# SNAC_7ch_SNES_in_Housing.net
KiCad netlist of a schematic drawn in EAGLE
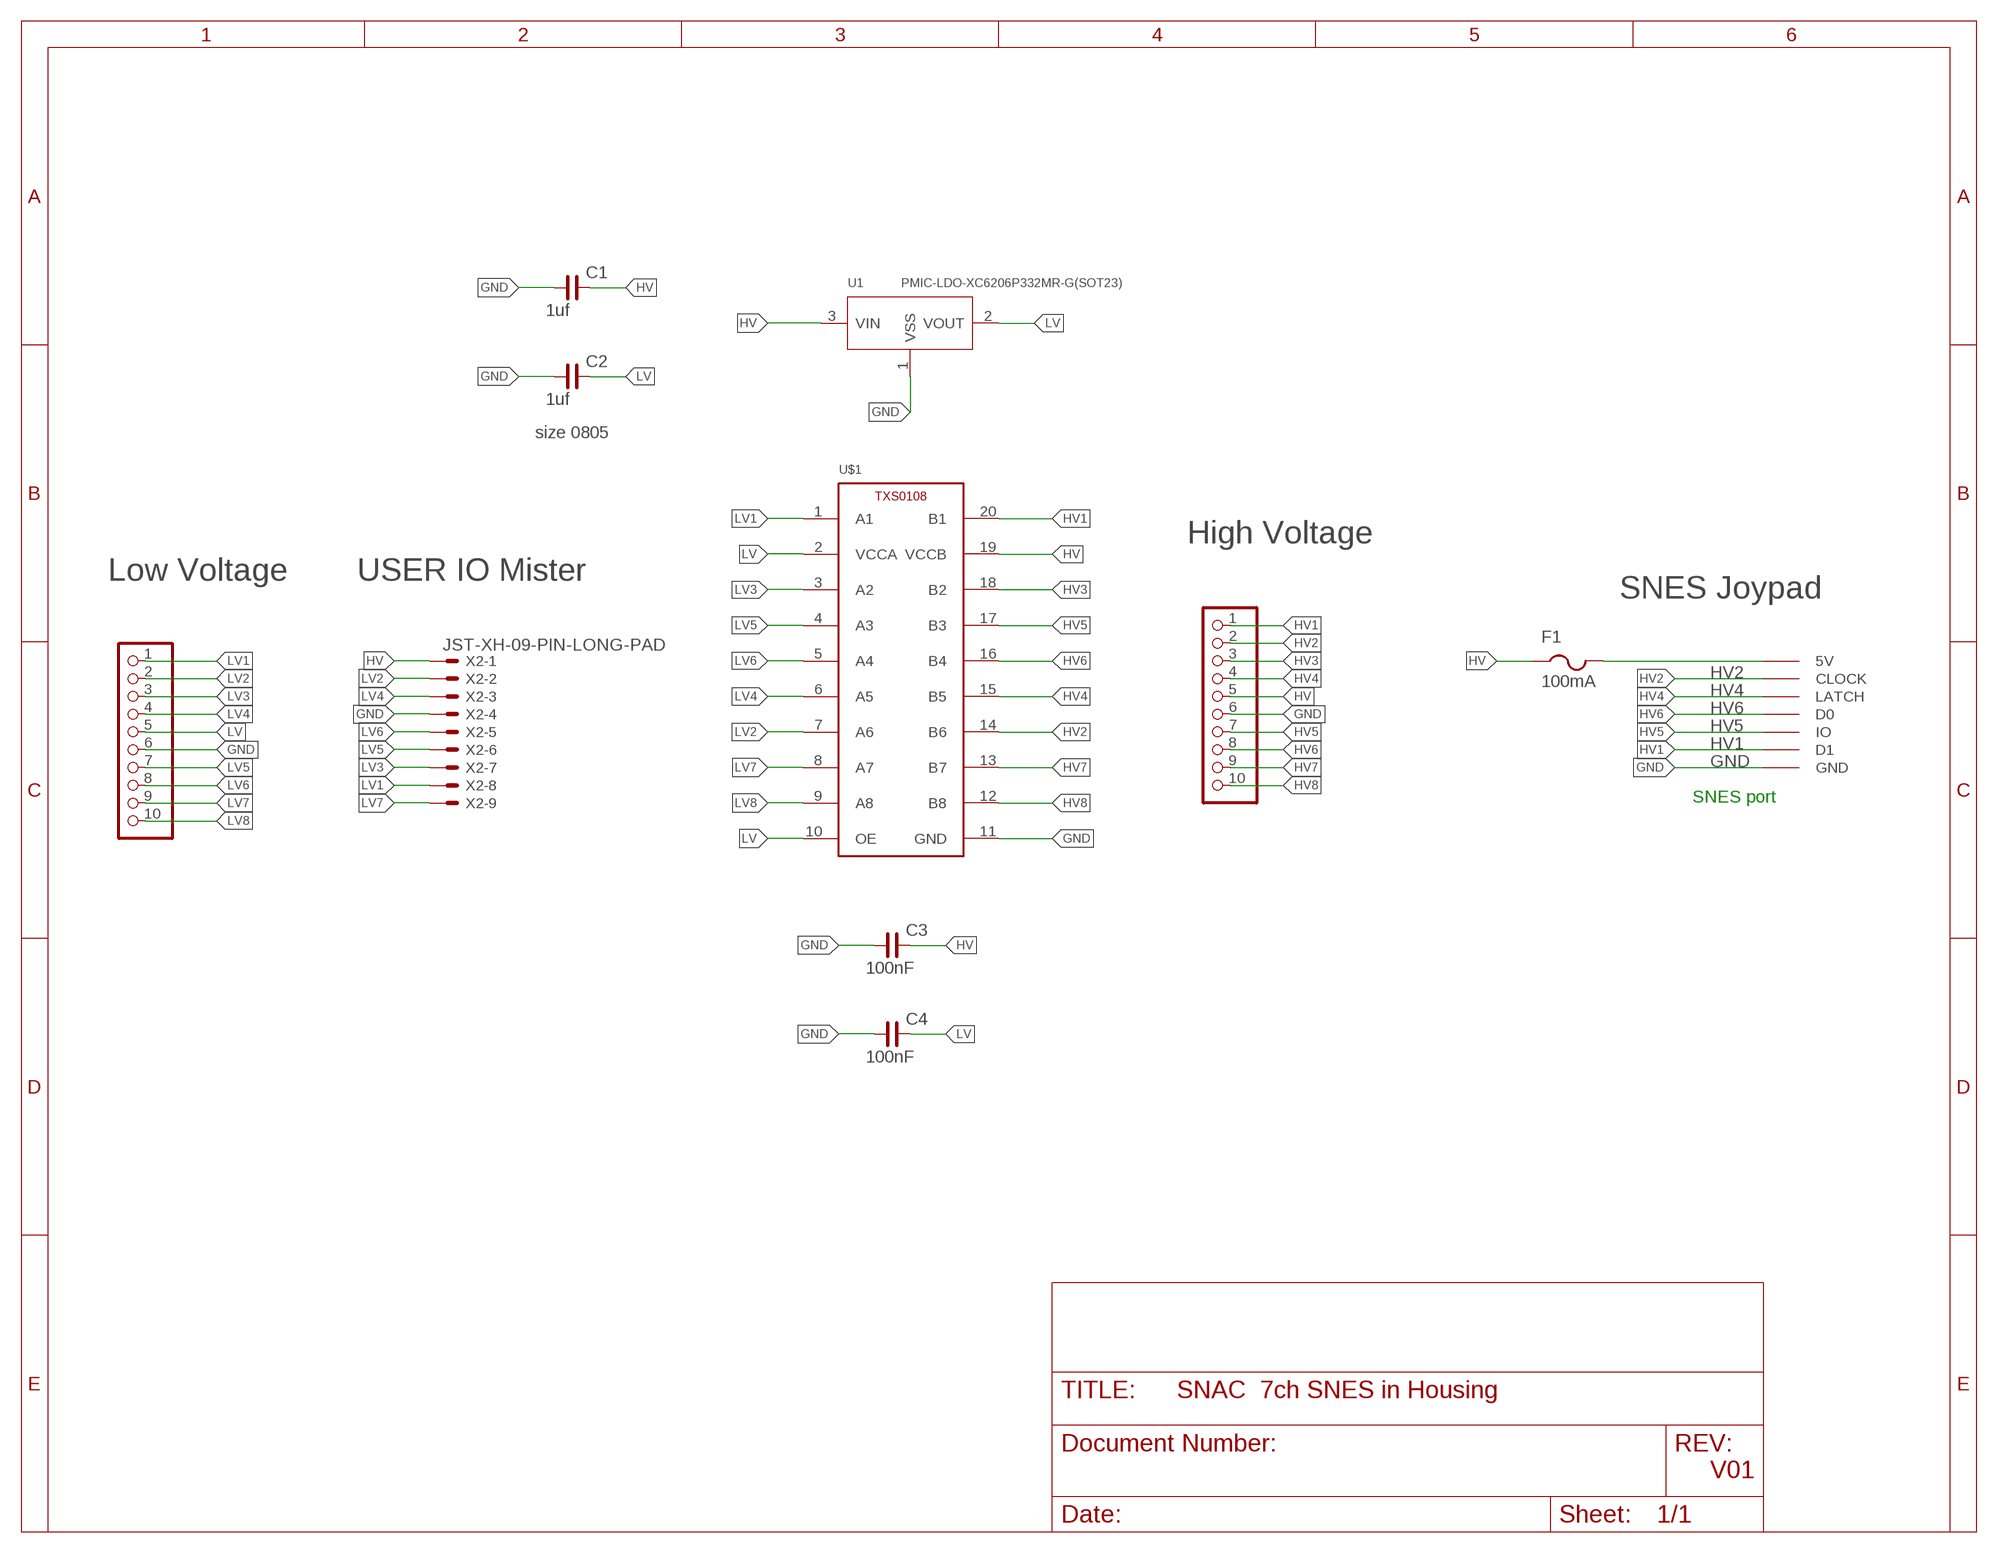
[diagram p0: schematic, sheet 1]

(export (version "E")
  (design (tool "Eeschema 10.0.6"))
  (components
    (comp (ref "C1")
      (value "1uf")
      (footprint "eagle-import:C0805")
      (libsource (lib "eagle-import") (part "C_0805"))
    )
    (comp (ref "C2")
      (value "1uf")
      (footprint "eagle-import:C0805")
      (libsource (lib "eagle-import") (part "C_0805"))
    )
    (comp (ref "C3")
      (value "100nF")
      (footprint "eagle-import:C0805")
      (libsource (lib "eagle-import") (part "C_0805"))
    )
    (comp (ref "C4")
      (value "100nF")
      (footprint "eagle-import:C0805")
      (libsource (lib "eagle-import") (part "C_0805"))
    )
    (comp (ref "F1")
      (value "100mA")
      (footprint "eagle-import:R1206")
      (libsource (lib "eagle-import") (part "PTCFUSE-1206"))
    )
    (comp (ref "JP1")
      (value "PINHD-1X10_2.54-S")
      (footprint "eagle-import:1X10-S")
      (libsource (lib "eagle-import") (part "PINHD-1X10_2.54-S"))
    )
    (comp (ref "JP2")
      (value "PINHD-1X10_2.54-S")
      (footprint "eagle-import:1X10-S")
      (libsource (lib "eagle-import") (part "PINHD-1X10_2.54-S"))
    )
    (comp (ref "U$1")
      (value "TXS0108")
      (footprint "eagle-import:R-PUSON-N20")
      (libsource (lib "eagle-import") (part "TXS0108"))
    )
    (comp (ref "U$3")
      (value "SNESCONN")
      (footprint "eagle-import:SNESCONN")
      (libsource (lib "eagle-import") (part "SNESCONN"))
    )
    (comp (ref "U1")
      (value "PMIC-LDO-XC6206P332MR-G(SOT23)")
      (footprint "eagle-import:SOT-23")
      (fields (field (name "MF") "Torex") (field (name "MP") "XC6206P332MR-G"))
      (libsource (lib "eagle-import") (part "PMIC-LDO-XC6206P332MR-G(SOT23)"))
    )
    (comp (ref "X2")
      (value "JST-XH-09-PIN-LONG-PAD")
      (footprint "eagle-import:JST-XH-09-PACKAGE-LONG-PAD")
      (libsource (lib "eagle-import") (part "JST-XH-09-PIN-LONG-PAD"))
    )
  )
  (nets
    (net (code "1") (name "GND") (class "Default")
      (node (ref "C1") (pin "1") (pinfunction "1_1") (pintype "passive"))
      (node (ref "C2") (pin "1") (pinfunction "1_1") (pintype "passive"))
      (node (ref "C3") (pin "1") (pinfunction "1_1") (pintype "passive"))
      (node (ref "C4") (pin "1") (pinfunction "1_1") (pintype "passive"))
      (node (ref "JP1") (pin "6") (pinfunction "6_6") (pintype "passive"))
      (node (ref "JP2") (pin "6") (pinfunction "6_6") (pintype "passive"))
      (node (ref "U$1") (pin "11") (pinfunction "GND_11") (pintype "bidirectional"))
      (node (ref "U$3") (pin "GND") (pinfunction "GND_GND") (pintype "power_in"))
      (node (ref "U1") (pin "1") (pinfunction "VSS_1") (pintype "power_in"))
      (node (ref "X2") (pin "4") (pinfunction "S_4") (pintype "passive"))
    )
    (net (code "2") (name "HV") (class "Default")
      (node (ref "C1") (pin "2") (pinfunction "2_2") (pintype "passive"))
      (node (ref "C3") (pin "2") (pinfunction "2_2") (pintype "passive"))
      (node (ref "F1") (pin "1") (pinfunction "1_1") (pintype "passive"))
      (node (ref "JP2") (pin "5") (pinfunction "5_5") (pintype "passive"))
      (node (ref "U$1") (pin "19") (pinfunction "VCCB_19") (pintype "bidirectional"))
      (node (ref "U1") (pin "3") (pinfunction "VIN_3") (pintype "input"))
      (node (ref "X2") (pin "1") (pinfunction "S_1") (pintype "passive"))
    )
    (net (code "3") (name "HV1") (class "Default")
      (node (ref "JP2") (pin "1") (pinfunction "1_1") (pintype "passive"))
      (node (ref "U$1") (pin "20") (pinfunction "B1_20") (pintype "bidirectional"))
      (node (ref "U$3") (pin "D1") (pinfunction "D1_D1") (pintype "bidirectional"))
    )
    (net (code "4") (name "HV2") (class "Default")
      (node (ref "JP2") (pin "2") (pinfunction "2_2") (pintype "passive"))
      (node (ref "U$1") (pin "14") (pinfunction "B6_14") (pintype "bidirectional"))
      (node (ref "U$3") (pin "CLOCK") (pinfunction "CLOCK_CLOCK") (pintype "input"))
    )
    (net (code "5") (name "HV3") (class "Default")
      (node (ref "JP2") (pin "3") (pinfunction "3_3") (pintype "passive"))
      (node (ref "U$1") (pin "18") (pinfunction "B2_18") (pintype "bidirectional"))
    )
    (net (code "6") (name "HV4") (class "Default")
      (node (ref "JP2") (pin "4") (pinfunction "4_4") (pintype "passive"))
      (node (ref "U$1") (pin "15") (pinfunction "B5_15") (pintype "bidirectional"))
      (node (ref "U$3") (pin "LATCH") (pinfunction "LATCH_LATCH") (pintype "input"))
    )
    (net (code "7") (name "HV5") (class "Default")
      (node (ref "JP2") (pin "7") (pinfunction "7_7") (pintype "passive"))
      (node (ref "U$1") (pin "17") (pinfunction "B3_17") (pintype "bidirectional"))
      (node (ref "U$3") (pin "IO") (pinfunction "IO_IO") (pintype "bidirectional"))
    )
    (net (code "8") (name "HV6") (class "Default")
      (node (ref "JP2") (pin "8") (pinfunction "8_8") (pintype "passive"))
      (node (ref "U$1") (pin "16") (pinfunction "B4_16") (pintype "bidirectional"))
      (node (ref "U$3") (pin "D0") (pinfunction "D0_D0") (pintype "bidirectional"))
    )
    (net (code "9") (name "HV7") (class "Default")
      (node (ref "JP2") (pin "9") (pinfunction "9_9") (pintype "passive"))
      (node (ref "U$1") (pin "13") (pinfunction "B7_13") (pintype "bidirectional"))
    )
    (net (code "10") (name "HV8") (class "Default")
      (node (ref "JP2") (pin "10") (pinfunction "10_10") (pintype "passive"))
      (node (ref "U$1") (pin "12") (pinfunction "B8_12") (pintype "bidirectional"))
    )
    (net (code "11") (name "LV") (class "Default")
      (node (ref "C2") (pin "2") (pinfunction "2_2") (pintype "passive"))
      (node (ref "C4") (pin "2") (pinfunction "2_2") (pintype "passive"))
      (node (ref "JP1") (pin "5") (pinfunction "5_5") (pintype "passive"))
      (node (ref "U$1") (pin "10") (pinfunction "OE_10") (pintype "bidirectional"))
      (node (ref "U$1") (pin "2") (pinfunction "VCCA_2") (pintype "bidirectional"))
      (node (ref "U1") (pin "2") (pinfunction "VOUT_2") (pintype "output"))
    )
    (net (code "12") (name "LV1") (class "Default")
      (node (ref "JP1") (pin "1") (pinfunction "1_1") (pintype "passive"))
      (node (ref "U$1") (pin "1") (pinfunction "A1_1") (pintype "bidirectional"))
      (node (ref "X2") (pin "8") (pinfunction "S_8") (pintype "passive"))
    )
    (net (code "13") (name "LV2") (class "Default")
      (node (ref "JP1") (pin "2") (pinfunction "2_2") (pintype "passive"))
      (node (ref "U$1") (pin "7") (pinfunction "A6_7") (pintype "bidirectional"))
      (node (ref "X2") (pin "2") (pinfunction "S_2") (pintype "passive"))
    )
    (net (code "14") (name "LV3") (class "Default")
      (node (ref "JP1") (pin "3") (pinfunction "3_3") (pintype "passive"))
      (node (ref "U$1") (pin "3") (pinfunction "A2_3") (pintype "bidirectional"))
      (node (ref "X2") (pin "7") (pinfunction "S_7") (pintype "passive"))
    )
    (net (code "15") (name "LV4") (class "Default")
      (node (ref "JP1") (pin "4") (pinfunction "4_4") (pintype "passive"))
      (node (ref "U$1") (pin "6") (pinfunction "A5_6") (pintype "bidirectional"))
      (node (ref "X2") (pin "3") (pinfunction "S_3") (pintype "passive"))
    )
    (net (code "16") (name "LV5") (class "Default")
      (node (ref "JP1") (pin "7") (pinfunction "7_7") (pintype "passive"))
      (node (ref "U$1") (pin "4") (pinfunction "A3_4") (pintype "bidirectional"))
      (node (ref "X2") (pin "6") (pinfunction "S_6") (pintype "passive"))
    )
    (net (code "17") (name "LV6") (class "Default")
      (node (ref "JP1") (pin "8") (pinfunction "8_8") (pintype "passive"))
      (node (ref "U$1") (pin "5") (pinfunction "A4_5") (pintype "bidirectional"))
      (node (ref "X2") (pin "5") (pinfunction "S_5") (pintype "passive"))
    )
    (net (code "18") (name "LV7") (class "Default")
      (node (ref "JP1") (pin "9") (pinfunction "9_9") (pintype "passive"))
      (node (ref "X2") (pin "9") (pinfunction "S_9") (pintype "passive"))
    )
    (net (code "19") (name "LV8") (class "Default")
      (node (ref "JP1") (pin "10") (pinfunction "10_10") (pintype "passive"))
      (node (ref "U$1") (pin "9") (pinfunction "A8_9") (pintype "bidirectional"))
    )
    (net (code "20") (name "Net-(F1-Pad2)") (class "Default")
      (node (ref "F1") (pin "2") (pinfunction "2_2") (pintype "passive"))
      (node (ref "U$3") (pin "5V") (pinfunction "5V_5V") (pintype "input"))
    )
    (net (code "21") (name "unconnected-(U$1-A7-Pad8)") (class "Default")
      (node (ref "U$1") (pin "8") (pinfunction "A7_8") (pintype "bidirectional"))
    )
  )
)
